# ProProject_Access_Control_KMX_Switch_202.net
KiCad netlist of a schematic drawn in EasyEDA Pro
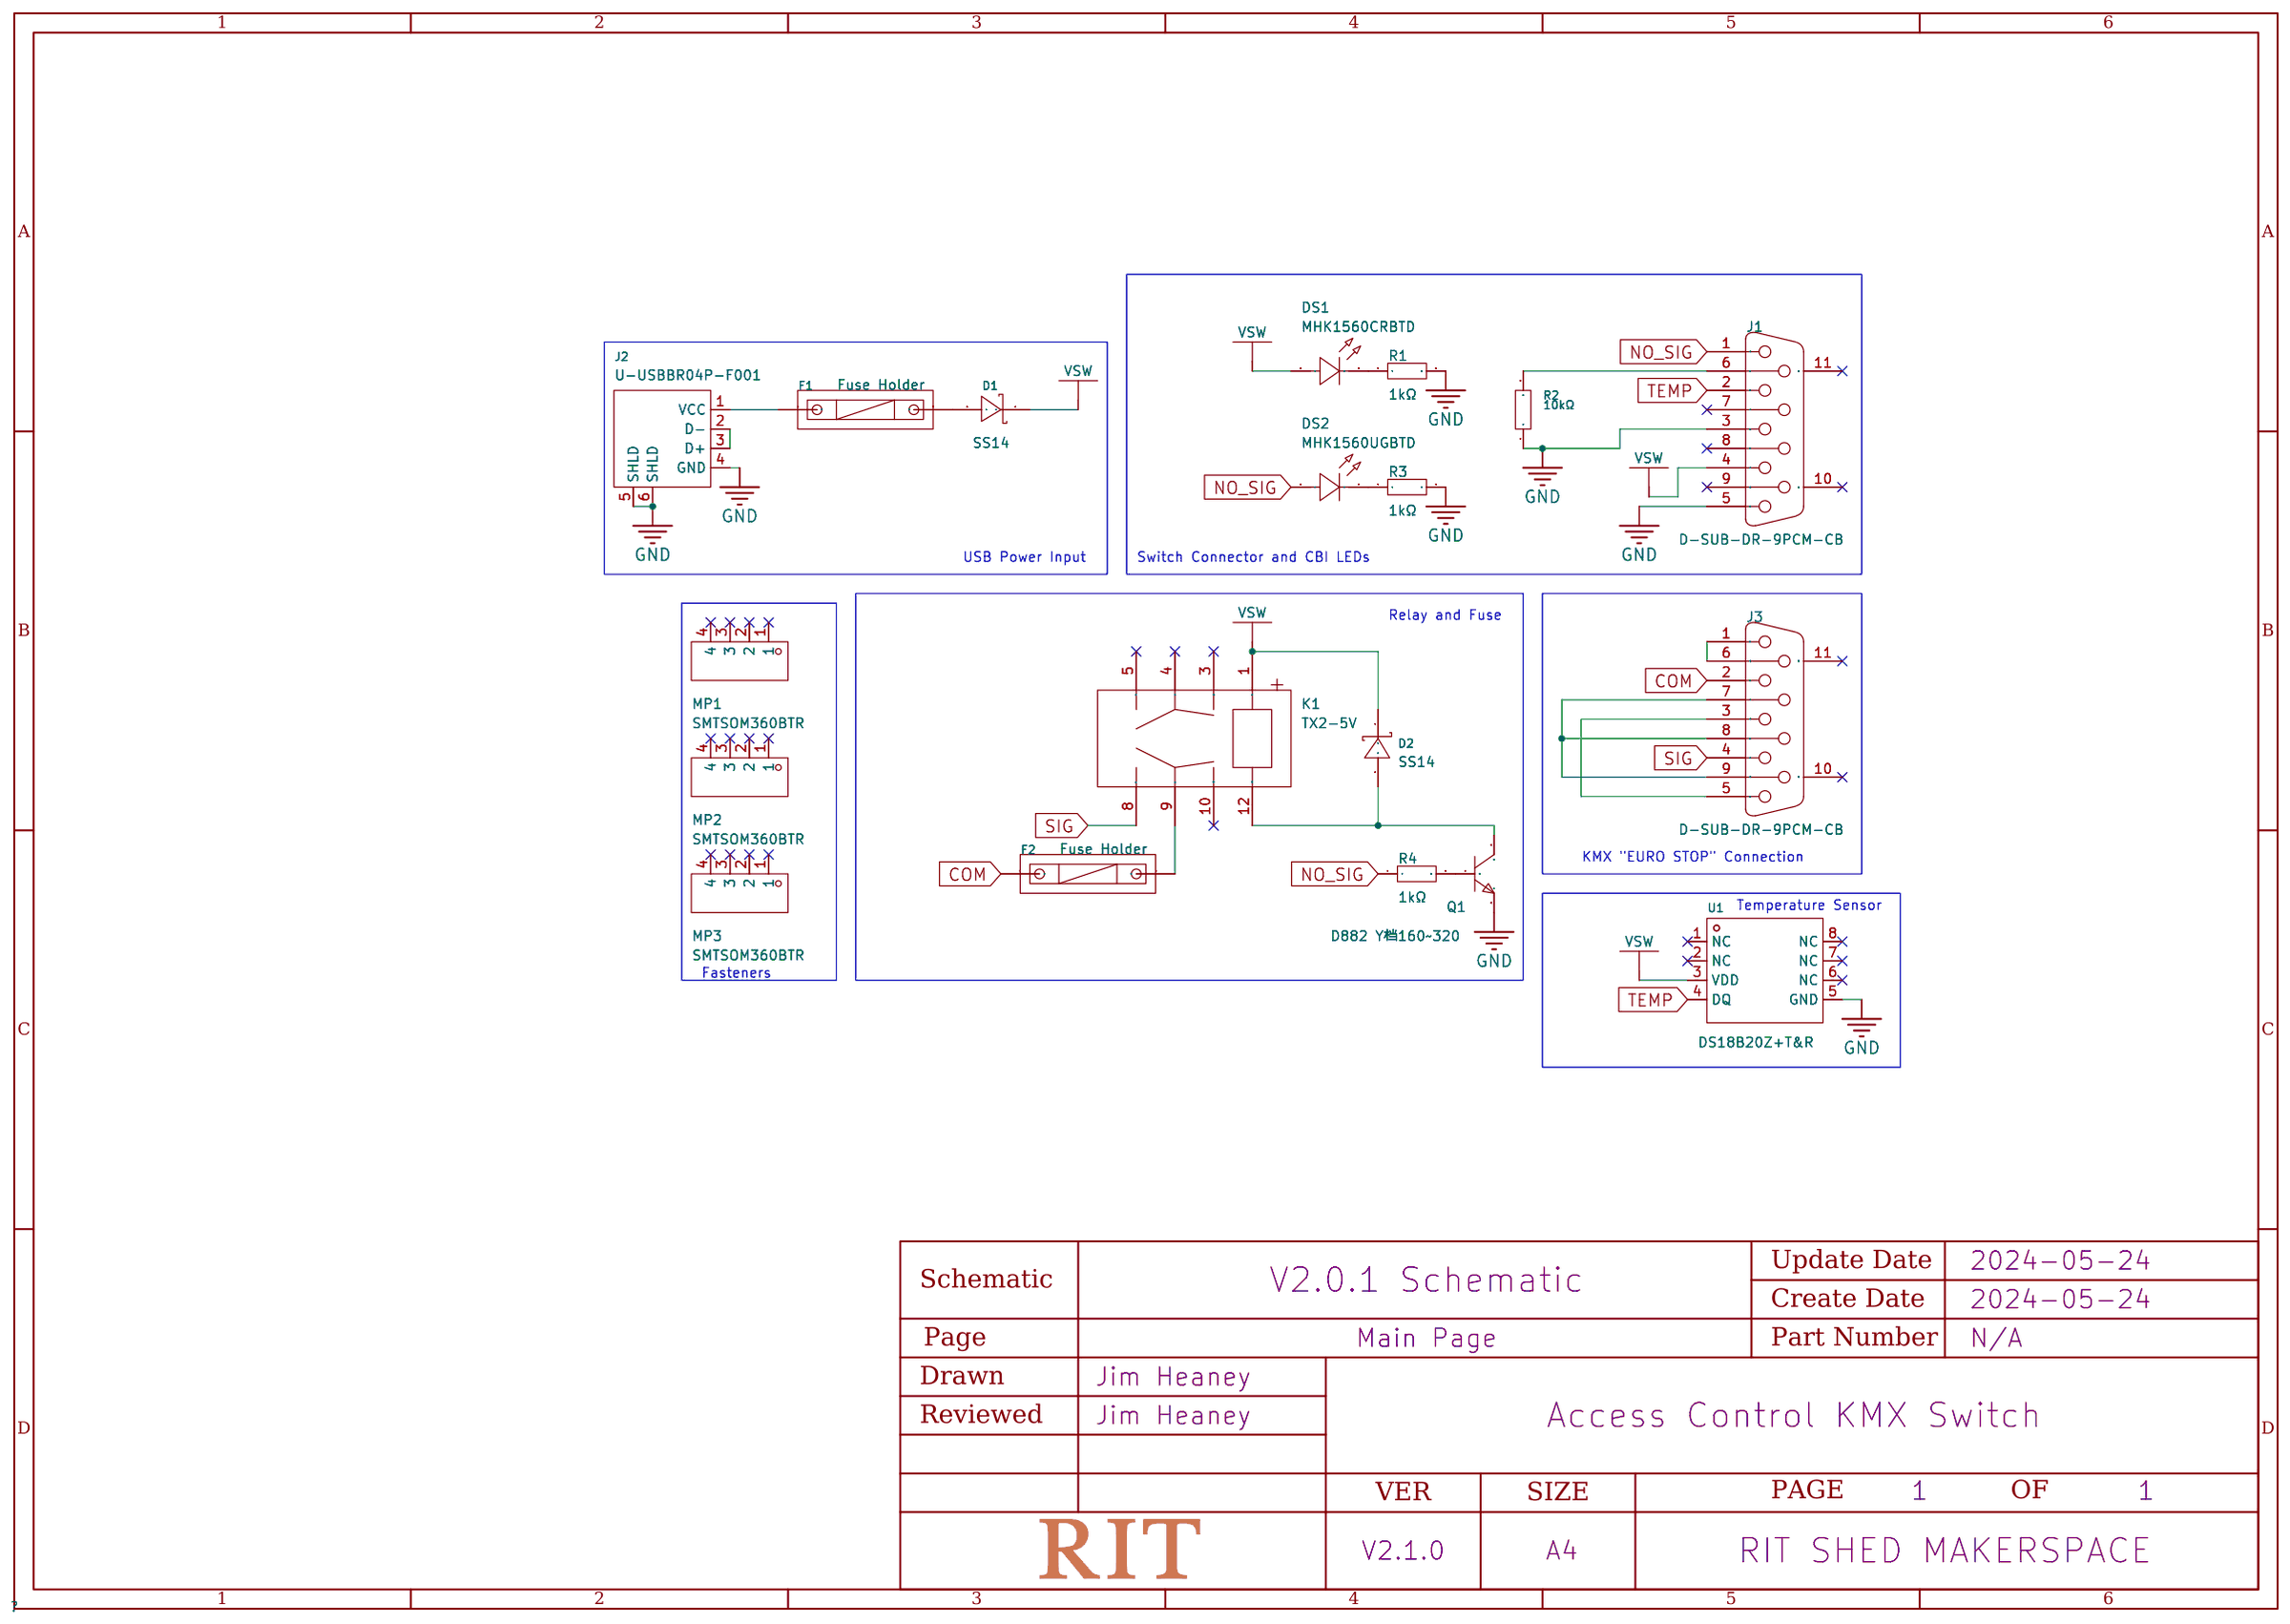
[diagram p0: schematic sheet]

(export (version "E")
  (design (tool "Eeschema 10.0.6"))
  (components
    (comp (ref "D1")
      (value "SS14")
      (footprint "easyedapro:SMA_L4.2-W2.6-LS5.3-RD")
      (fields (field (name "Manufacturer") "MDD"))
      (libsource (lib "easyedapro") (part "SS14"))
    )
    (comp (ref "D2")
      (value "SS14")
      (footprint "easyedapro:SMA_L4.2-W2.6-LS5.3-RD")
      (fields (field (name "Manufacturer") "MDD"))
      (libsource (lib "easyedapro") (part "SS14"))
    )
    (comp (ref "DS1")
      (value "MHK1560CRBTD")
      (footprint "easyedapro:LED-TH_MHK1560UGBTD")
      (fields (field (name "Manufacturer") "MEIHUA(美华)"))
      (libsource (lib "easyedapro") (part "MHK1560CGBTD"))
    )
    (comp (ref "DS2")
      (value "MHK1560UGBTD")
      (footprint "easyedapro:LED-TH_MHK1560UGBTD")
      (fields (field (name "Manufacturer") "MEIHUA(美华)"))
      (libsource (lib "easyedapro") (part "MHK1560UGBTD"))
    )
    (comp (ref "F1")
      (value "Fuse Holder")
      (footprint "easyedapro:FUSE-TH_L24.5-W9.8-P22.5")
      (description "Fuseholder Type:- Fuse Type:- Fuse Size:-")
      (fields (field (name "Manufacturer Part") "保险丝透明座") (field (name "Manufacturer") "xcfuse(旭程)"))
      (libsource (lib "easyedapro") (part "Fuse transparent seat"))
    )
    (comp (ref "F2")
      (value "Fuse Holder")
      (footprint "easyedapro:FUSE-TH_L24.5-W9.8-P22.5")
      (description "Fuseholder Type:- Fuse Type:- Fuse Size:-")
      (fields (field (name "Manufacturer Part") "保险丝透明座") (field (name "Manufacturer") "xcfuse(旭程)"))
      (libsource (lib "easyedapro") (part "Fuse transparent seat"))
    )
    (comp (ref "J1")
      (value "D-SUB-DR-9PCM-CB")
      (footprint "easyedapro:DB9-TH_ID09S33E4GV00LF")
      (fields (field (name "Manufacturer") "XUNPU(讯普)"))
      (libsource (lib "easyedapro") (part "D-SUB-DR-9PCM-CB"))
    )
    (comp (ref "J2")
      (value "U-USBBR04P-F001")
      (footprint "easyedapro:USB-B-TH_U241-041N-1BR85-1")
      (fields (field (name "Manufacturer") "Ckmtw(灿科盟)"))
      (libsource (lib "easyedapro") (part "U-USBBR04P-F001"))
    )
    (comp (ref "J3")
      (value "D-SUB-DR-9PCM-CB")
      (footprint "easyedapro:DB9-TH_ID09S33E4GV00LF")
      (fields (field (name "Manufacturer") "XUNPU(讯普)"))
      (libsource (lib "easyedapro") (part "D-SUB-DR-9PCM-CB"))
    )
    (comp (ref "K1")
      (value "TX2-5V")
      (footprint "easyedapro:RELAY-TH_TX2-3V")
      (fields (field (name "Manufacturer") "PANASONIC(松下)"))
      (libsource (lib "easyedapro") (part "TX2-5V"))
    )
    (comp (ref "MP1")
      (value "SMTSOM360BTR")
      (footprint "easyedapro:SMD_BD5.6-D4.1")
      (fields (field (name "Manufacturer") "YIYUAN(怡远)"))
      (libsource (lib "easyedapro") (part "SMTSOM360BTR"))
    )
    (comp (ref "MP2")
      (value "SMTSOM360BTR")
      (footprint "easyedapro:SMD_BD5.6-D4.1")
      (fields (field (name "Manufacturer") "YIYUAN(怡远)"))
      (libsource (lib "easyedapro") (part "SMTSOM360BTR"))
    )
    (comp (ref "MP3")
      (value "SMTSOM360BTR")
      (footprint "easyedapro:SMD_BD5.6-D4.1")
      (fields (field (name "Manufacturer") "YIYUAN(怡远)"))
      (libsource (lib "easyedapro") (part "SMTSOM360BTR"))
    )
    (comp (ref "Q1")
      (value "D882 Y档160~320")
      (footprint "easyedapro:SOT-89-3_L4.5-W2.5-P1.50-LS4.2-BR")
      (fields (field (name "Manufacturer") "CJ(江苏长电/长晶)"))
      (libsource (lib "easyedapro") (part "D882_C9634"))
    )
    (comp (ref "R1")
      (value "1kΩ")
      (footprint "easyedapro:R0805")
      (fields
        (field (name "Manufacturer Part") "0805W8F1001T5E")
        (field (name "Manufacturer") "UNI-ROYAL(厚声)")
      )
      (libsource (lib "easyedapro") (part "0805W8F1001T5E"))
    )
    (comp (ref "R2")
      (value "10kΩ")
      (footprint "easyedapro:R0805")
      (fields
        (field (name "Manufacturer Part") "0805W8F1002T5E")
        (field (name "Manufacturer") "UNI-ROYAL(厚声)")
      )
      (libsource (lib "easyedapro") (part "0805W8F1002T5E"))
    )
    (comp (ref "R3")
      (value "1kΩ")
      (footprint "easyedapro:R0805")
      (fields
        (field (name "Manufacturer Part") "0805W8F1001T5E")
        (field (name "Manufacturer") "UNI-ROYAL(厚声)")
      )
      (libsource (lib "easyedapro") (part "0805W8F1001T5E"))
    )
    (comp (ref "R4")
      (value "1kΩ")
      (footprint "easyedapro:R0805")
      (fields
        (field (name "Manufacturer Part") "0805W8F1001T5E")
        (field (name "Manufacturer") "UNI-ROYAL(厚声)")
      )
      (libsource (lib "easyedapro") (part "0805W8F1001T5E"))
    )
    (comp (ref "U1")
      (value "DS18B20Z+T&R")
      (footprint "easyedapro:SOIC-8_L4.9-W3.9-P1.27-LS6.0-BL")
      (description "Supply Voltage:3V~5.5V Supply Voltage:3V~5.5V")
      (fields (field (name "Manufacturer") "ADI(亚德诺)/MAXIM(美信)"))
      (libsource (lib "easyedapro") (part "DS18B20Z+T&amp;R"))
    )
  )
  (nets
    (net (code "1") (name "COM") (class "Default")
      (node (ref "F2") (pin "1") (pinfunction "1_1") (pintype "input"))
      (node (ref "J3") (pin "2") (pinfunction "2_2") (pintype "input"))
    )
    (net (code "2") (name "GND") (class "Default")
      (node (ref "J1") (pin "3") (pinfunction "3_3") (pintype "input"))
      (node (ref "J1") (pin "5") (pinfunction "5_5") (pintype "input"))
      (node (ref "J2") (pin "4") (pinfunction "GND_4") (pintype "input"))
      (node (ref "J2") (pin "5") (pinfunction "SHLD_5") (pintype "input"))
      (node (ref "J2") (pin "6") (pinfunction "SHLD_6") (pintype "input"))
      (node (ref "Q1") (pin "3") (pinfunction "E_3") (pintype "input"))
      (node (ref "R1") (pin "2") (pinfunction "2_2") (pintype "input"))
      (node (ref "R2") (pin "1") (pinfunction "1_1") (pintype "input"))
      (node (ref "R3") (pin "2") (pinfunction "2_2") (pintype "input"))
      (node (ref "U1") (pin "5") (pinfunction "GND_5") (pintype "input"))
    )
    (net (code "3") (name "NO_SIG") (class "Default")
      (node (ref "DS2") (pin "2") (pinfunction "A_2") (pintype "unspecified"))
      (node (ref "J1") (pin "1") (pinfunction "1_1") (pintype "input"))
      (node (ref "R4") (pin "1") (pinfunction "1_1") (pintype "input"))
    )
    (net (code "4") (name "Net-(D1-A)") (class "Default")
      (node (ref "D1") (pin "2") (pinfunction "A_2") (pintype "input"))
      (node (ref "F1") (pin "2") (pinfunction "2_2") (pintype "input"))
    )
    (net (code "5") (name "Net-(D2-A)") (class "Default")
      (node (ref "D2") (pin "2") (pinfunction "A_2") (pintype "input"))
      (node (ref "K1") (pin "12") (pinfunction "12_12") (pintype "input"))
      (node (ref "Q1") (pin "2") (pinfunction "C_2") (pintype "input"))
    )
    (net (code "6") (name "Net-(DS1-K)") (class "Default")
      (node (ref "DS1") (pin "1") (pinfunction "K_1") (pintype "unspecified"))
      (node (ref "R1") (pin "1") (pinfunction "1_1") (pintype "input"))
    )
    (net (code "7") (name "Net-(DS2-K)") (class "Default")
      (node (ref "DS2") (pin "1") (pinfunction "K_1") (pintype "unspecified"))
      (node (ref "R3") (pin "1") (pinfunction "1_1") (pintype "input"))
    )
    (net (code "8") (name "Net-(F2-Pad2)") (class "Default")
      (node (ref "F2") (pin "2") (pinfunction "2_2") (pintype "input"))
      (node (ref "K1") (pin "9") (pinfunction "9_9") (pintype "input"))
    )
    (net (code "9") (name "Net-(J1-Pad6)") (class "Default")
      (node (ref "J1") (pin "6") (pinfunction "6_6") (pintype "input"))
      (node (ref "R2") (pin "2") (pinfunction "2_2") (pintype "input"))
    )
    (net (code "10") (name "Net-(J2-D+)") (class "Default")
      (node (ref "J2") (pin "2") (pinfunction "D-_2") (pintype "input"))
      (node (ref "J2") (pin "3") (pinfunction "D+_3") (pintype "input"))
    )
    (net (code "11") (name "Net-(J2-VCC)") (class "Default")
      (node (ref "F1") (pin "1") (pinfunction "1_1") (pintype "input"))
      (node (ref "J2") (pin "1") (pinfunction "VCC_1") (pintype "input"))
    )
    (net (code "12") (name "Net-(J3-Pad1)") (class "Default")
      (node (ref "J3") (pin "1") (pinfunction "1_1") (pintype "input"))
      (node (ref "J3") (pin "6") (pinfunction "6_6") (pintype "input"))
    )
    (net (code "13") (name "Net-(J3-Pad3)") (class "Default")
      (node (ref "J3") (pin "3") (pinfunction "3_3") (pintype "input"))
      (node (ref "J3") (pin "5") (pinfunction "5_5") (pintype "input"))
    )
    (net (code "14") (name "Net-(J3-Pad7)") (class "Default")
      (node (ref "J3") (pin "7") (pinfunction "7_7") (pintype "input"))
      (node (ref "J3") (pin "8") (pinfunction "8_8") (pintype "input"))
      (node (ref "J3") (pin "9") (pinfunction "9_9") (pintype "input"))
    )
    (net (code "15") (name "Net-(Q1-B)") (class "Default")
      (node (ref "Q1") (pin "1") (pinfunction "B_1") (pintype "input"))
      (node (ref "R4") (pin "2") (pinfunction "2_2") (pintype "input"))
    )
    (net (code "16") (name "SIG") (class "Default")
      (node (ref "J3") (pin "4") (pinfunction "4_4") (pintype "input"))
      (node (ref "K1") (pin "8") (pinfunction "8_8") (pintype "input"))
    )
    (net (code "17") (name "TEMP") (class "Default")
      (node (ref "J1") (pin "2") (pinfunction "2_2") (pintype "input"))
      (node (ref "U1") (pin "4") (pinfunction "DQ_4") (pintype "input"))
    )
    (net (code "18") (name "VSW") (class "Default")
      (node (ref "D1") (pin "1") (pinfunction "K_1") (pintype "input"))
      (node (ref "D2") (pin "1") (pinfunction "K_1") (pintype "input"))
      (node (ref "DS1") (pin "2") (pinfunction "A_2") (pintype "unspecified"))
      (node (ref "J1") (pin "4") (pinfunction "4_4") (pintype "input"))
      (node (ref "K1") (pin "1") (pinfunction "1_1") (pintype "input"))
      (node (ref "U1") (pin "3") (pinfunction "VDD_3") (pintype "input"))
    )
    (net (code "19") (name "unconnected-(J1-MH1-Pad10)") (class "Default")
      (node (ref "J1") (pin "10") (pinfunction "MH1_10") (pintype "input+no_connect"))
    )
    (net (code "20") (name "unconnected-(J1-MH2-Pad11)") (class "Default")
      (node (ref "J1") (pin "11") (pinfunction "MH2_11") (pintype "input+no_connect"))
    )
    (net (code "21") (name "unconnected-(J1-Pad7)") (class "Default")
      (node (ref "J1") (pin "7") (pinfunction "7_7") (pintype "input+no_connect"))
    )
    (net (code "22") (name "unconnected-(J1-Pad8)") (class "Default")
      (node (ref "J1") (pin "8") (pinfunction "8_8") (pintype "input+no_connect"))
    )
    (net (code "23") (name "unconnected-(J1-Pad9)") (class "Default")
      (node (ref "J1") (pin "9") (pinfunction "9_9") (pintype "input+no_connect"))
    )
    (net (code "24") (name "unconnected-(J3-MH1-Pad10)") (class "Default")
      (node (ref "J3") (pin "10") (pinfunction "MH1_10") (pintype "input+no_connect"))
    )
    (net (code "25") (name "unconnected-(J3-MH2-Pad11)") (class "Default")
      (node (ref "J3") (pin "11") (pinfunction "MH2_11") (pintype "input+no_connect"))
    )
    (net (code "26") (name "unconnected-(K1-Pad3)") (class "Default")
      (node (ref "K1") (pin "3") (pinfunction "3_3") (pintype "input+no_connect"))
    )
    (net (code "27") (name "unconnected-(K1-Pad4)") (class "Default")
      (node (ref "K1") (pin "4") (pinfunction "4_4") (pintype "input+no_connect"))
    )
    (net (code "28") (name "unconnected-(K1-Pad5)") (class "Default")
      (node (ref "K1") (pin "5") (pinfunction "5_5") (pintype "input+no_connect"))
    )
    (net (code "29") (name "unconnected-(K1-Pad10)") (class "Default")
      (node (ref "K1") (pin "10") (pinfunction "10_10") (pintype "input+no_connect"))
    )
    (net (code "30") (name "unconnected-(MP1-Pad1)") (class "Default")
      (node (ref "MP1") (pin "1") (pinfunction "1_1") (pintype "unspecified+no_connect"))
    )
    (net (code "31") (name "unconnected-(MP1-Pad2)") (class "Default")
      (node (ref "MP1") (pin "2") (pinfunction "2_2") (pintype "unspecified+no_connect"))
    )
    (net (code "32") (name "unconnected-(MP1-Pad3)") (class "Default")
      (node (ref "MP1") (pin "3") (pinfunction "3_3") (pintype "unspecified+no_connect"))
    )
    (net (code "33") (name "unconnected-(MP1-Pad4)") (class "Default")
      (node (ref "MP1") (pin "4") (pinfunction "4_4") (pintype "unspecified+no_connect"))
    )
    (net (code "34") (name "unconnected-(MP2-Pad1)") (class "Default")
      (node (ref "MP2") (pin "1") (pinfunction "1_1") (pintype "unspecified+no_connect"))
    )
    (net (code "35") (name "unconnected-(MP2-Pad2)") (class "Default")
      (node (ref "MP2") (pin "2") (pinfunction "2_2") (pintype "unspecified+no_connect"))
    )
    (net (code "36") (name "unconnected-(MP2-Pad3)") (class "Default")
      (node (ref "MP2") (pin "3") (pinfunction "3_3") (pintype "unspecified+no_connect"))
    )
    (net (code "37") (name "unconnected-(MP2-Pad4)") (class "Default")
      (node (ref "MP2") (pin "4") (pinfunction "4_4") (pintype "unspecified+no_connect"))
    )
    (net (code "38") (name "unconnected-(MP3-Pad1)") (class "Default")
      (node (ref "MP3") (pin "1") (pinfunction "1_1") (pintype "unspecified+no_connect"))
    )
    (net (code "39") (name "unconnected-(MP3-Pad2)") (class "Default")
      (node (ref "MP3") (pin "2") (pinfunction "2_2") (pintype "unspecified+no_connect"))
    )
    (net (code "40") (name "unconnected-(MP3-Pad3)") (class "Default")
      (node (ref "MP3") (pin "3") (pinfunction "3_3") (pintype "unspecified+no_connect"))
    )
    (net (code "41") (name "unconnected-(MP3-Pad4)") (class "Default")
      (node (ref "MP3") (pin "4") (pinfunction "4_4") (pintype "unspecified+no_connect"))
    )
    (net (code "42") (name "unconnected-(U1-NC-Pad1)") (class "Default")
      (node (ref "U1") (pin "1") (pinfunction "NC_1") (pintype "input+no_connect"))
    )
    (net (code "43") (name "unconnected-(U1-NC-Pad2)") (class "Default")
      (node (ref "U1") (pin "2") (pinfunction "NC_2") (pintype "input+no_connect"))
    )
    (net (code "44") (name "unconnected-(U1-NC-Pad6)") (class "Default")
      (node (ref "U1") (pin "6") (pinfunction "NC_6") (pintype "input+no_connect"))
    )
    (net (code "45") (name "unconnected-(U1-NC-Pad7)") (class "Default")
      (node (ref "U1") (pin "7") (pinfunction "NC_7") (pintype "input+no_connect"))
    )
    (net (code "46") (name "unconnected-(U1-NC-Pad8)") (class "Default")
      (node (ref "U1") (pin "8") (pinfunction "NC_8") (pintype "input+no_connect"))
    )
  )
)
